# sb-sonata-usbphy.net
KiCad netlist of a schematic drawn in Altium Designer
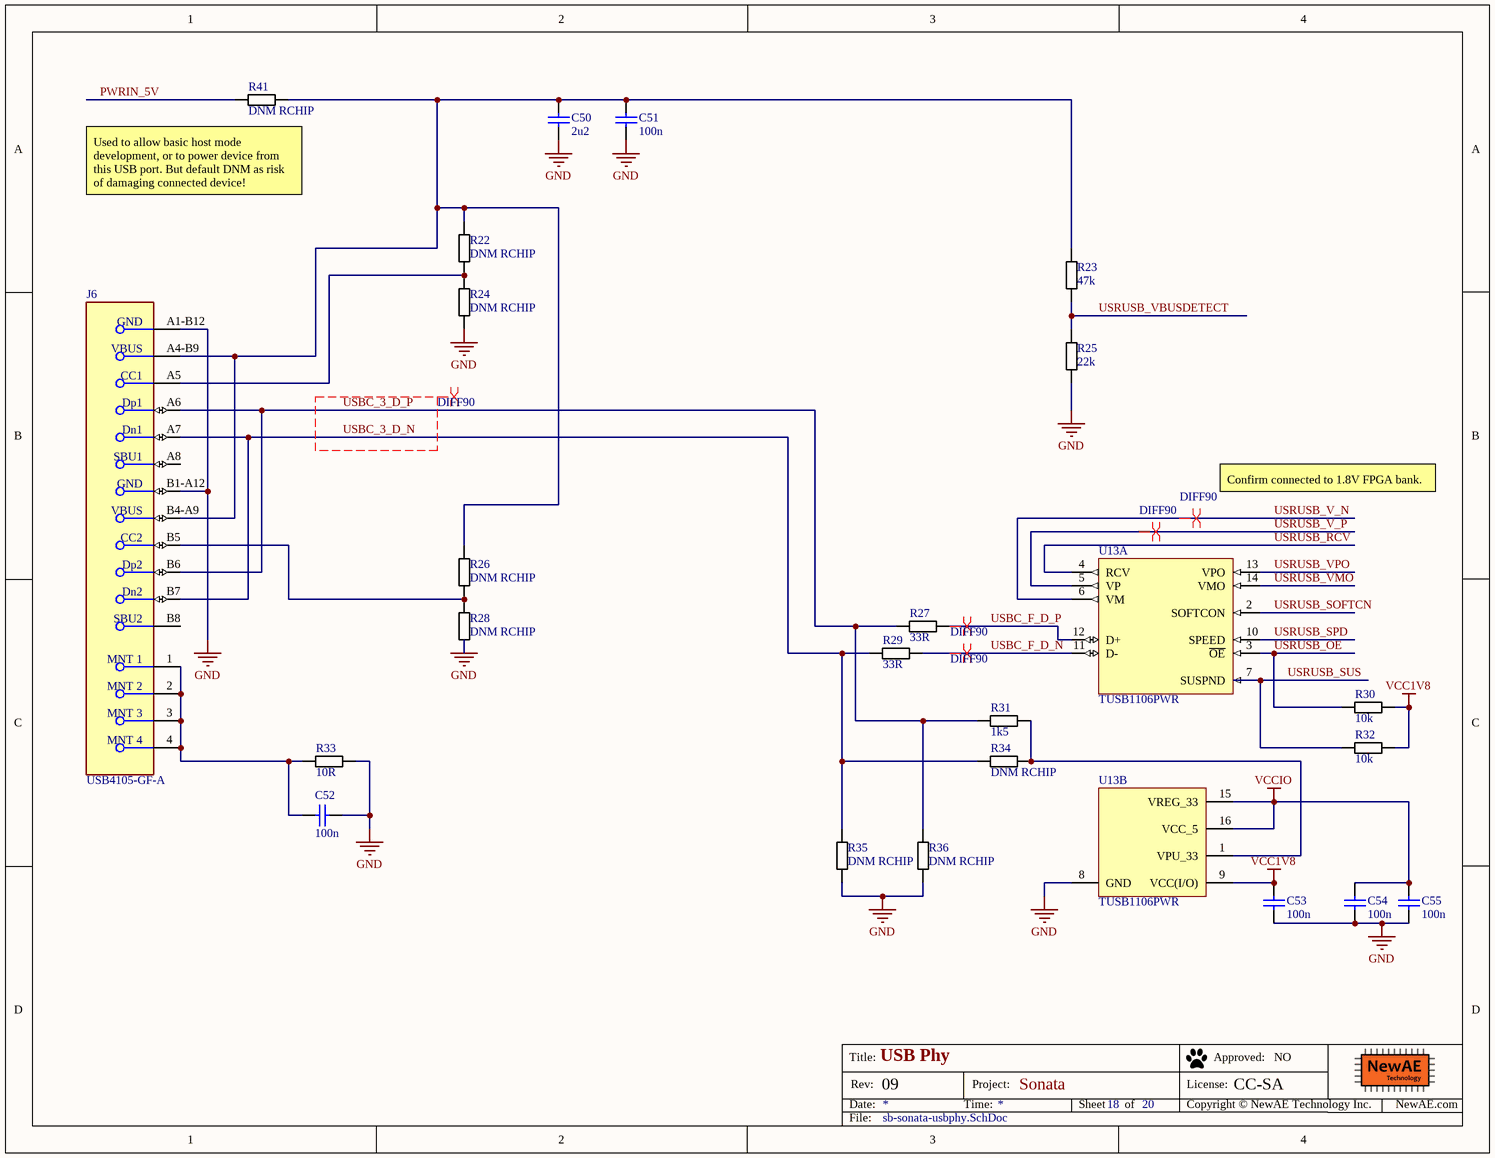
[diagram p0: sb-sonata-usbphy.SchDoc]

(export (version "E")
  (design (tool "Eeschema 10.0.6"))
  (components
    (comp (ref "C50")
      (value "2u2")
      (footprint "CAPC0603_M")
      (description "2u2, 0603")
      (fields (field (name "PART NUMBER") "CCHIP-2u2-0603"))
      (libsource (lib "NewAE_AltiumLib") (part "CAP"))
    )
    (comp (ref "C51")
      (value "100n")
      (footprint "CAPC0402_M")
      (description "100n, 0402")
      (fields (field (name "PART NUMBER") "CCHIP-100n-0402"))
      (libsource (lib "NewAE_AltiumLib") (part "CAP"))
    )
    (comp (ref "C52")
      (value "100n")
      (footprint "CAPC0603_M")
      (description "100n, 0603")
      (fields (field (name "PART NUMBER") "CCHIP-100n-0603"))
      (libsource (lib "NewAE_AltiumLib") (part "CAP"))
    )
    (comp (ref "C53")
      (value "100n")
      (footprint "CAPC0402_M")
      (description "100n, 0402")
      (fields (field (name "PART NUMBER") "CCHIP-100n-0402"))
      (libsource (lib "NewAE_AltiumLib") (part "CAP"))
    )
    (comp (ref "C54")
      (value "100n")
      (footprint "CAPC0402_M")
      (description "100n, 0402")
      (fields (field (name "PART NUMBER") "CCHIP-100n-0402"))
      (libsource (lib "NewAE_AltiumLib") (part "CAP"))
    )
    (comp (ref "C55")
      (value "100n")
      (footprint "CAPC0402_M")
      (description "100n, 0402")
      (fields (field (name "PART NUMBER") "CCHIP-100n-0402"))
      (libsource (lib "NewAE_AltiumLib") (part "CAP"))
    )
    (comp (ref "J6")
      (value "USB4105-GF-A")
      (footprint "FP-USB4105-GF-A-MFG")
      (description "CONN RCPT USB2.0 TYPEC 5A")
      (fields
        (field (name "MANUFACTURER") "GCT")
        (field (name "OCTOPART") "https://octopart.com/usb4105-gf-a-gct-106627878")
      )
      (libsource (lib "Altium Content Vault") (part "e7c17a616881a82b79941196b4bec10"))
    )
    (comp (ref "R22")
      (value "DNM RCHIP")
      (footprint "RESC1608X55N")
      (description "Do Not Mount Resistor")
      (fields (field (name "PART NUMBER") "RCHIP-DNM-0603"))
      (libsource (lib "") (part "RES-EU_2"))
    )
    (comp (ref "R23")
      (value "47k")
      (footprint "RESC1005X40N")
      (description "47k res, 0402, 1%, 1/16W")
      (fields (field (name "PART NUMBER") "RCHIP-47K-0402") (field (name "TOLERANCE") "1%"))
      (libsource (lib "") (part "RES-EU_2"))
    )
    (comp (ref "R24")
      (value "DNM RCHIP")
      (footprint "RESC1608X55N")
      (description "Do Not Mount Resistor")
      (fields (field (name "PART NUMBER") "RCHIP-DNM-0603"))
      (libsource (lib "") (part "RES-EU_2"))
    )
    (comp (ref "R25")
      (value "22k")
      (footprint "RESC1005X40N")
      (description "22k res, 0402, 1%, 1/16W")
      (fields (field (name "PART NUMBER") "RCHIP-22K-0402") (field (name "TOLERANCE") "1%"))
      (libsource (lib "") (part "RES-EU_2"))
    )
    (comp (ref "R26")
      (value "DNM RCHIP")
      (footprint "RESC1608X55N")
      (description "Do Not Mount Resistor")
      (fields (field (name "PART NUMBER") "RCHIP-DNM-0603"))
      (libsource (lib "") (part "RES-EU_2"))
    )
    (comp (ref "R27")
      (value "33R")
      (footprint "RESC1608X55N")
      (description "33R res, 0603, 1%, 1/10W")
      (fields (field (name "PART NUMBER") "RCHIP-33R-0603") (field (name "TOLERANCE") "1%"))
      (libsource (lib "") (part "RES-EU_1"))
    )
    (comp (ref "R28")
      (value "DNM RCHIP")
      (footprint "RESC1608X55N")
      (description "Do Not Mount Resistor")
      (fields (field (name "PART NUMBER") "RCHIP-DNM-0603"))
      (libsource (lib "") (part "RES-EU_2"))
    )
    (comp (ref "R29")
      (value "33R")
      (footprint "RESC1608X55N")
      (description "33R res, 0603, 1%, 1/10W")
      (fields (field (name "PART NUMBER") "RCHIP-33R-0603") (field (name "TOLERANCE") "1%"))
      (libsource (lib "") (part "RES-EU_1"))
    )
    (comp (ref "R30")
      (value "10k")
      (footprint "RESC1005X40N")
      (description "10k res, 0402, 1%, 1/16W")
      (fields (field (name "PART NUMBER") "RCHIP-10K-0402") (field (name "TOLERANCE") "1%"))
      (libsource (lib "") (part "RES-EU_1"))
    )
    (comp (ref "R31")
      (value "1k5")
      (footprint "RESC1608X55N")
      (description "1k5 res, 0603, 1%, 1/10W")
      (fields (field (name "PART NUMBER") "RCHIP-1K5-0603") (field (name "TOLERANCE") "1%"))
      (libsource (lib "") (part "RES-EU_1"))
    )
    (comp (ref "R32")
      (value "10k")
      (footprint "RESC1005X40N")
      (description "10k res, 0402, 1%, 1/16W")
      (fields (field (name "PART NUMBER") "RCHIP-10K-0402") (field (name "TOLERANCE") "1%"))
      (libsource (lib "") (part "RES-EU_1"))
    )
    (comp (ref "R33")
      (value "10R")
      (footprint "RESC1608X55N")
      (description "10R res, 0603, 1%, 1/10W")
      (fields (field (name "PART NUMBER") "RCHIP-10R-0603") (field (name "TOLERANCE") "1%"))
      (libsource (lib "") (part "RES-EU_1"))
    )
    (comp (ref "R34")
      (value "DNM RCHIP")
      (footprint "RESC1608X55N")
      (description "Do Not Mount Resistor")
      (fields (field (name "PART NUMBER") "RCHIP-DNM-0603"))
      (libsource (lib "") (part "RES-EU_1"))
    )
    (comp (ref "R35")
      (value "DNM RCHIP")
      (footprint "RESC1608X55N")
      (description "Do Not Mount Resistor")
      (fields (field (name "PART NUMBER") "RCHIP-DNM-0603"))
      (libsource (lib "") (part "RES-EU_3"))
    )
    (comp (ref "R36")
      (value "DNM RCHIP")
      (footprint "RESC1608X55N")
      (description "Do Not Mount Resistor")
      (fields (field (name "PART NUMBER") "RCHIP-DNM-0603"))
      (libsource (lib "") (part "RES-EU_3"))
    )
    (comp (ref "R41")
      (value "DNM RCHIP")
      (footprint "RESC1608X55N")
      (description "Do Not Mount Resistor")
      (fields (field (name "PART NUMBER") "RCHIP-DNM-0603"))
      (libsource (lib "NewAE_AltiumLib") (part "RES-EU"))
    )
    (comp (ref "U13")
      (value "TUSB1106PWR")
      (footprint "PW0016A_L")
      (fields (field (name "MANUFACTURER") "Texas Instruments"))
      (libsource (lib "Altium Content Vault") (part "TI-TUSB1106-TSSOP_PW-16"))
    )
  )
  (nets
    (net (code "1") (name "/PWRIN_5V") (class "Default")
      (node (ref "R41") (pin "2") (pinfunction "2_2") (pintype "passive"))
    )
    (net (code "2") (name "/USBC_3_D_N") (class "Default")
      (node (ref "J6") (pin "A7") (pinfunction "Dn1_A7") (pintype "bidirectional"))
      (node (ref "J6") (pin "B7") (pinfunction "Dn2_B7") (pintype "bidirectional"))
      (node (ref "R29") (pin "1") (pinfunction "1_1") (pintype "passive"))
      (node (ref "R34") (pin "1") (pinfunction "1_1") (pintype "passive"))
      (node (ref "R35") (pin "2") (pinfunction "2_2") (pintype "passive"))
    )
    (net (code "3") (name "/USBC_3_D_P") (class "Default")
      (node (ref "J6") (pin "A6") (pinfunction "Dp1_A6") (pintype "bidirectional"))
      (node (ref "J6") (pin "B6") (pinfunction "Dp2_B6") (pintype "bidirectional"))
      (node (ref "R27") (pin "1") (pinfunction "1_1") (pintype "passive"))
      (node (ref "R31") (pin "1") (pinfunction "1_1") (pintype "passive"))
      (node (ref "R36") (pin "2") (pinfunction "2_2") (pintype "passive"))
    )
    (net (code "4") (name "/USBC_F_D_N") (class "Default")
      (node (ref "R29") (pin "2") (pinfunction "2_2") (pintype "passive"))
      (node (ref "U13") (pin "11") (pinfunction "D-_11") (pintype "bidirectional"))
    )
    (net (code "5") (name "/USBC_F_D_P") (class "Default")
      (node (ref "R27") (pin "2") (pinfunction "2_2") (pintype "passive"))
      (node (ref "U13") (pin "12") (pinfunction "D+_12") (pintype "bidirectional"))
    )
    (net (code "6") (name "/USRUSB_OE") (class "Default")
      (node (ref "R30") (pin "1") (pinfunction "1_1") (pintype "passive"))
      (node (ref "U13") (pin "3") (pinfunction "~{OE}_3") (pintype "input"))
    )
    (net (code "7") (name "/USRUSB_RCV") (class "Default")
      (node (ref "U13") (pin "4") (pinfunction "RCV_4") (pintype "output"))
    )
    (net (code "8") (name "/USRUSB_SOFTCN") (class "Default")
      (node (ref "U13") (pin "2") (pinfunction "SOFTCON_2") (pintype "input"))
    )
    (net (code "9") (name "/USRUSB_SPD") (class "Default")
      (node (ref "U13") (pin "10") (pinfunction "SPEED_10") (pintype "input"))
    )
    (net (code "10") (name "/USRUSB_SUS") (class "Default")
      (node (ref "R32") (pin "1") (pinfunction "1_1") (pintype "passive"))
      (node (ref "U13") (pin "7") (pinfunction "SUSPND_7") (pintype "input"))
    )
    (net (code "11") (name "/USRUSB_VBUSDETECT") (class "Default")
      (node (ref "R23") (pin "2") (pinfunction "2_2") (pintype "passive"))
      (node (ref "R25") (pin "1") (pinfunction "1_1") (pintype "passive"))
    )
    (net (code "12") (name "/USRUSB_VMO") (class "Default")
      (node (ref "U13") (pin "14") (pinfunction "VMO_14") (pintype "input"))
    )
    (net (code "13") (name "/USRUSB_VPO") (class "Default")
      (node (ref "U13") (pin "13") (pinfunction "VPO_13") (pintype "input"))
    )
    (net (code "14") (name "/USRUSB_V_N") (class "Default")
      (node (ref "U13") (pin "6") (pinfunction "VM_6") (pintype "output"))
    )
    (net (code "15") (name "/USRUSB_V_P") (class "Default")
      (node (ref "U13") (pin "5") (pinfunction "VP_5") (pintype "output"))
    )
    (net (code "16") (name "GND") (class "Default")
      (node (ref "C50") (pin "2") (pinfunction "2_2") (pintype "passive"))
      (node (ref "C51") (pin "2") (pinfunction "2_2") (pintype "passive"))
      (node (ref "C52") (pin "2") (pinfunction "2_2") (pintype "passive"))
      (node (ref "C53") (pin "2") (pinfunction "2_2") (pintype "passive"))
      (node (ref "C54") (pin "2") (pinfunction "2_2") (pintype "passive"))
      (node (ref "C55") (pin "2") (pinfunction "2_2") (pintype "passive"))
      (node (ref "J6") (pin "A1-B12") (pinfunction "GND_A1-B12") (pintype "power_in"))
      (node (ref "J6") (pin "B1-A12") (pinfunction "GND_B1-A12") (pintype "bidirectional"))
      (node (ref "R24") (pin "2") (pinfunction "2_2") (pintype "passive"))
      (node (ref "R25") (pin "2") (pinfunction "2_2") (pintype "passive"))
      (node (ref "R28") (pin "2") (pinfunction "2_2") (pintype "passive"))
      (node (ref "R33") (pin "2") (pinfunction "2_2") (pintype "passive"))
      (node (ref "R35") (pin "1") (pinfunction "1_1") (pintype "passive"))
      (node (ref "R36") (pin "1") (pinfunction "1_1") (pintype "passive"))
      (node (ref "U13") (pin "8") (pinfunction "GND_8") (pintype "power_in"))
    )
    (net (code "17") (name "Net-(C50-Pad1)") (class "Default")
      (node (ref "C50") (pin "1") (pinfunction "1_1") (pintype "passive"))
      (node (ref "C51") (pin "1") (pinfunction "1_1") (pintype "passive"))
      (node (ref "J6") (pin "A4-B9") (pinfunction "VBUS_A4-B9") (pintype "power_in"))
      (node (ref "J6") (pin "B4-A9") (pinfunction "VBUS_B4-A9") (pintype "bidirectional"))
      (node (ref "R22") (pin "1") (pinfunction "1_1") (pintype "passive"))
      (node (ref "R23") (pin "1") (pinfunction "1_1") (pintype "passive"))
      (node (ref "R26") (pin "1") (pinfunction "1_1") (pintype "passive"))
      (node (ref "R41") (pin "1") (pinfunction "1_1") (pintype "passive"))
    )
    (net (code "18") (name "Net-(J6-CC1)") (class "Default")
      (node (ref "J6") (pin "A5") (pinfunction "CC1_A5") (pintype "power_in"))
      (node (ref "R22") (pin "2") (pinfunction "2_2") (pintype "passive"))
      (node (ref "R24") (pin "1") (pinfunction "1_1") (pintype "passive"))
    )
    (net (code "19") (name "Net-(J6-CC2)") (class "Default")
      (node (ref "J6") (pin "B5") (pinfunction "CC2_B5") (pintype "bidirectional"))
      (node (ref "R26") (pin "2") (pinfunction "2_2") (pintype "passive"))
      (node (ref "R28") (pin "1") (pinfunction "1_1") (pintype "passive"))
    )
    (net (code "20") (name "Net-(J6-MNT_1)") (class "Default")
      (node (ref "C52") (pin "1") (pinfunction "1_1") (pintype "passive"))
      (node (ref "J6") (pin "1") (pinfunction "MNT_1_1") (pintype "power_in"))
      (node (ref "J6") (pin "2") (pinfunction "MNT_2_2") (pintype "power_in"))
      (node (ref "J6") (pin "3") (pinfunction "MNT_3_3") (pintype "power_in"))
      (node (ref "J6") (pin "4") (pinfunction "MNT_4_4") (pintype "power_in"))
      (node (ref "R33") (pin "1") (pinfunction "1_1") (pintype "passive"))
    )
    (net (code "21") (name "Net-(U13B-VPU_33)") (class "Default")
      (node (ref "R31") (pin "2") (pinfunction "2_2") (pintype "passive"))
      (node (ref "R34") (pin "2") (pinfunction "2_2") (pintype "passive"))
      (node (ref "U13") (pin "1") (pinfunction "VPU_33_1") (pintype "power_in"))
    )
    (net (code "22") (name "VCC1V8") (class "Default")
      (node (ref "C53") (pin "1") (pinfunction "1_1") (pintype "passive"))
      (node (ref "R30") (pin "2") (pinfunction "2_2") (pintype "passive"))
      (node (ref "R32") (pin "2") (pinfunction "2_2") (pintype "passive"))
      (node (ref "U13") (pin "9") (pinfunction "VCC(I/O)_9") (pintype "power_in"))
    )
    (net (code "23") (name "VCCIO") (class "Default")
      (node (ref "C54") (pin "1") (pinfunction "1_1") (pintype "passive"))
      (node (ref "C55") (pin "1") (pinfunction "1_1") (pintype "passive"))
      (node (ref "U13") (pin "15") (pinfunction "VREG_33_15") (pintype "power_in"))
      (node (ref "U13") (pin "16") (pinfunction "VCC_5_16") (pintype "power_in"))
    )
    (net (code "24") (name "unconnected-(J6-SBU1-PadA8)") (class "Default")
      (node (ref "J6") (pin "A8") (pinfunction "SBU1_A8") (pintype "bidirectional"))
    )
    (net (code "25") (name "unconnected-(J6-SBU2-PadB8)") (class "Default")
      (node (ref "J6") (pin "B8") (pinfunction "SBU2_B8") (pintype "power_in"))
    )
  )
)
